# mtsch.net
KiCad netlist of a schematic drawn in EAGLE
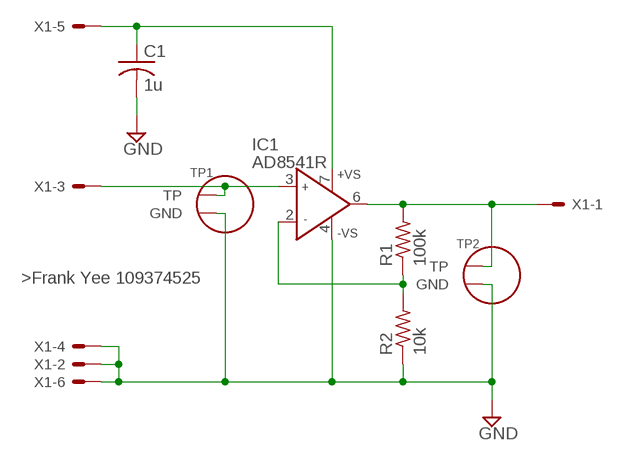
[diagram p0: schematic, sheet 1]

(export (version "E")
  (design (tool "Eeschema 10.0.6"))
  (components
    (comp (ref "C1")
      (value "1u")
      (footprint "eagle-import:C3216")
      (libsource (lib "eagle-import") (part "C-USC3216"))
    )
    (comp (ref "IC1")
      (value "AD8541R")
      (footprint "eagle-import:SO8")
      (fields (field (name "MPN") "AD8541ARZ"))
      (libsource (lib "eagle-import") (part "AD8541R"))
    )
    (comp (ref "R1")
      (value "100k")
      (footprint "eagle-import:M2012")
      (libsource (lib "eagle-import") (part "R-US_M2012"))
    )
    (comp (ref "R2")
      (value "10k")
      (footprint "eagle-import:M2012")
      (libsource (lib "eagle-import") (part "R-US_M2012"))
    )
    (comp (ref "TP1")
      (value "TESTPOINT")
      (footprint "eagle-import:TPXPACK")
      (libsource (lib "eagle-import") (part "TESTPOINT"))
    )
    (comp (ref "TP2")
      (value "TESTPOINT")
      (footprint "eagle-import:TPXPACK")
      (libsource (lib "eagle-import") (part "TESTPOINT"))
    )
    (comp (ref "X1")
      (value "22-23-2061")
      (footprint "eagle-import:22-23-2061")
      (fields (field (name "MF") "MOLEX"))
      (libsource (lib "eagle-import") (part "22-23-2061"))
    )
  )
  (nets
    (net (code "1") (name "GND") (class "Default")
      (node (ref "C1") (pin "2") (pinfunction "2_2") (pintype "passive"))
      (node (ref "IC1") (pin "4") (pinfunction "-VS_4") (pintype "input"))
      (node (ref "R2") (pin "1") (pinfunction "1_1") (pintype "passive"))
      (node (ref "TP1") (pin "GND") (pinfunction "GND_GND") (pintype "power_in"))
      (node (ref "TP2") (pin "GND") (pinfunction "GND_GND") (pintype "power_in"))
      (node (ref "X1") (pin "2") (pinfunction "S_2") (pintype "passive"))
      (node (ref "X1") (pin "4") (pinfunction "S_4") (pintype "passive"))
      (node (ref "X1") (pin "6") (pinfunction "S_6") (pintype "passive"))
    )
    (net (code "2") (name "Net-(IC1-+VS)") (class "Default")
      (node (ref "C1") (pin "1") (pinfunction "1_1") (pintype "passive"))
      (node (ref "IC1") (pin "7") (pinfunction "+VS_7") (pintype "input"))
      (node (ref "X1") (pin "5") (pinfunction "S_5") (pintype "passive"))
    )
    (net (code "3") (name "Net-(IC1-IN+)") (class "Default")
      (node (ref "IC1") (pin "3") (pinfunction "IN+_3") (pintype "input"))
      (node (ref "TP1") (pin "TP") (pinfunction "TP_TP") (pintype "input"))
      (node (ref "X1") (pin "3") (pinfunction "S_3") (pintype "passive"))
    )
    (net (code "4") (name "Net-(IC1-IN-)") (class "Default")
      (node (ref "IC1") (pin "2") (pinfunction "IN-_2") (pintype "input"))
      (node (ref "R1") (pin "1") (pinfunction "1_1") (pintype "passive"))
      (node (ref "R2") (pin "2") (pinfunction "2_2") (pintype "passive"))
    )
    (net (code "5") (name "Net-(IC1-OUT)") (class "Default")
      (node (ref "IC1") (pin "6") (pinfunction "OUT_6") (pintype "output"))
      (node (ref "R1") (pin "2") (pinfunction "2_2") (pintype "passive"))
      (node (ref "TP2") (pin "TP") (pinfunction "TP_TP") (pintype "input"))
      (node (ref "X1") (pin "1") (pinfunction "S_1") (pintype "passive"))
    )
  )
)
